# amp_ins.net
KiCad netlist of a schematic drawn in EAGLE
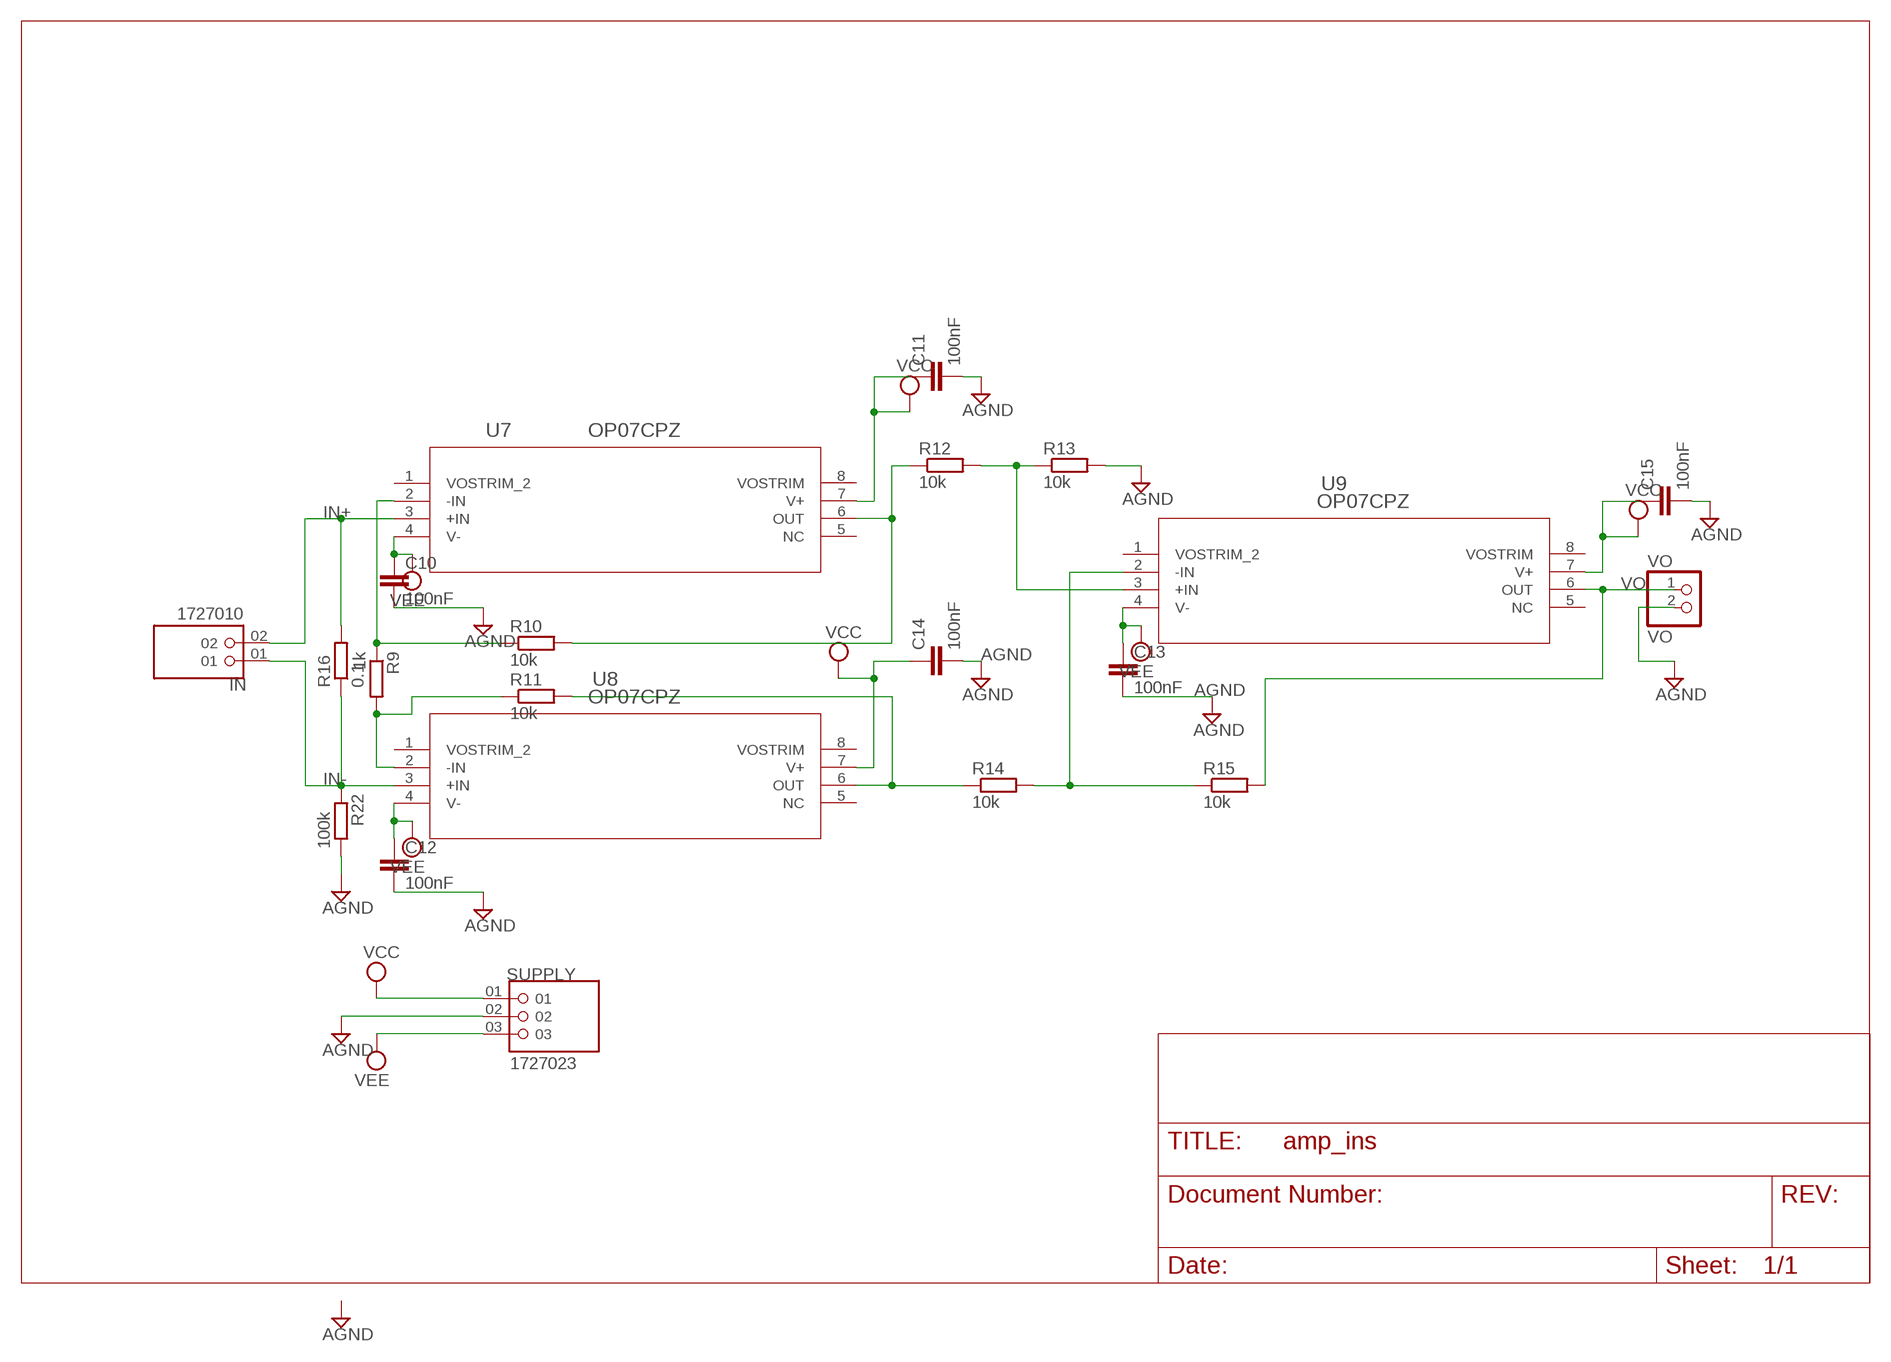
[diagram p0: schematic, sheet 1]

(export (version "E")
  (design (tool "Eeschema 10.0.6"))
  (components
    (comp (ref "C10")
      (value "100nF")
      (footprint "eagle-import:C075-042X103")
      (libsource (lib "eagle-import") (part "C-EU075-042X103"))
    )
    (comp (ref "C11")
      (value "100nF")
      (footprint "eagle-import:C075-042X103")
      (libsource (lib "eagle-import") (part "C-EU075-042X103"))
    )
    (comp (ref "C12")
      (value "100nF")
      (footprint "eagle-import:C075-042X103")
      (libsource (lib "eagle-import") (part "C-EU075-042X103"))
    )
    (comp (ref "C13")
      (value "100nF")
      (footprint "eagle-import:C075-042X103")
      (libsource (lib "eagle-import") (part "C-EU075-042X103"))
    )
    (comp (ref "C14")
      (value "100nF")
      (footprint "eagle-import:C075-042X103")
      (libsource (lib "eagle-import") (part "C-EU075-042X103"))
    )
    (comp (ref "C15")
      (value "100nF")
      (footprint "eagle-import:C075-042X103")
      (libsource (lib "eagle-import") (part "C-EU075-042X103"))
    )
    (comp (ref "IN")
      (value "1727010")
      (footprint "eagle-import:PHOENIX_1727010")
      (fields (field (name "MANUFACTURER") "Phoenix Contact"))
      (libsource (lib "eagle-import") (part "1727010"))
    )
    (comp (ref "R9")
      (value "1k")
      (footprint "eagle-import:0207_10")
      (libsource (lib "eagle-import") (part "R-EU_0207/10"))
    )
    (comp (ref "R10")
      (value "10k")
      (footprint "eagle-import:0207_10")
      (libsource (lib "eagle-import") (part "R-EU_0207/10"))
    )
    (comp (ref "R11")
      (value "10k")
      (footprint "eagle-import:0207_10")
      (libsource (lib "eagle-import") (part "R-EU_0207/10"))
    )
    (comp (ref "R12")
      (value "10k")
      (footprint "eagle-import:0207_10")
      (libsource (lib "eagle-import") (part "R-EU_0207/10"))
    )
    (comp (ref "R13")
      (value "10k")
      (footprint "eagle-import:0207_10")
      (libsource (lib "eagle-import") (part "R-EU_0207/10"))
    )
    (comp (ref "R14")
      (value "10k")
      (footprint "eagle-import:0207_10")
      (libsource (lib "eagle-import") (part "R-EU_0207/10"))
    )
    (comp (ref "R15")
      (value "10k")
      (footprint "eagle-import:0207_10")
      (libsource (lib "eagle-import") (part "R-EU_0207/10"))
    )
    (comp (ref "R16")
      (value "0.1")
      (footprint "eagle-import:0617_17")
      (libsource (lib "eagle-import") (part "R-EU_0617/17"))
    )
    (comp (ref "R22")
      (value "100k")
      (footprint "eagle-import:0207_10")
      (libsource (lib "eagle-import") (part "R-EU_0207/10"))
    )
    (comp (ref "SUPPLY")
      (value "1727023")
      (footprint "eagle-import:PHOENIX_1727023")
      (fields (field (name "MANUFACTURER") "Phoenix Contact"))
      (libsource (lib "eagle-import") (part "1727023"))
    )
    (comp (ref "U7")
      (value "OP07CPZ")
      (footprint "eagle-import:N_8_ADI")
      (fields (field (name "COPYRIGHT") "Copyright (C) 2024 Ultra Librarian. All rights reserved."))
      (libsource (lib "eagle-import") (part "OP07CPZ"))
    )
    (comp (ref "U8")
      (value "OP07CPZ")
      (footprint "eagle-import:N_8_ADI")
      (fields (field (name "COPYRIGHT") "Copyright (C) 2024 Ultra Librarian. All rights reserved."))
      (libsource (lib "eagle-import") (part "OP07CPZ"))
    )
    (comp (ref "U9")
      (value "OP07CPZ")
      (footprint "eagle-import:N_8_ADI")
      (fields (field (name "COPYRIGHT") "Copyright (C) 2024 Ultra Librarian. All rights reserved."))
      (libsource (lib "eagle-import") (part "OP07CPZ"))
    )
    (comp (ref "VO")
      (value "VO")
      (footprint "eagle-import:1X02")
      (libsource (lib "eagle-import") (part "PINHD-1X2"))
    )
  )
  (nets
    (net (code "1") (name "/IN+") (class "Default")
      (node (ref "IN") (pin "02") (pinfunction "02_02") (pintype "passive"))
      (node (ref "R16") (pin "2") (pinfunction "2_2") (pintype "passive"))
      (node (ref "U7") (pin "3") (pinfunction "+IN_3") (pintype "passive"))
    )
    (net (code "2") (name "/IN-") (class "Default")
      (node (ref "IN") (pin "01") (pinfunction "01_01") (pintype "passive"))
      (node (ref "R16") (pin "1") (pinfunction "1_1") (pintype "passive"))
      (node (ref "R22") (pin "1") (pinfunction "1_1") (pintype "passive"))
      (node (ref "U8") (pin "3") (pinfunction "+IN_3") (pintype "passive"))
    )
    (net (code "3") (name "/VO") (class "Default")
      (node (ref "R15") (pin "2") (pinfunction "2_2") (pintype "passive"))
      (node (ref "U9") (pin "6") (pinfunction "OUT_6") (pintype "passive"))
      (node (ref "VO") (pin "1") (pinfunction "1_1") (pintype "passive"))
    )
    (net (code "4") (name "AGND") (class "Default")
      (node (ref "C10") (pin "2") (pinfunction "2_2") (pintype "passive"))
      (node (ref "C11") (pin "2") (pinfunction "2_2") (pintype "passive"))
      (node (ref "C12") (pin "2") (pinfunction "2_2") (pintype "passive"))
      (node (ref "C13") (pin "2") (pinfunction "2_2") (pintype "passive"))
      (node (ref "C14") (pin "2") (pinfunction "2_2") (pintype "passive"))
      (node (ref "C15") (pin "2") (pinfunction "2_2") (pintype "passive"))
      (node (ref "R13") (pin "2") (pinfunction "2_2") (pintype "passive"))
      (node (ref "R22") (pin "2") (pinfunction "2_2") (pintype "passive"))
      (node (ref "SUPPLY") (pin "02") (pinfunction "02_02") (pintype "passive"))
      (node (ref "VO") (pin "2") (pinfunction "2_2") (pintype "passive"))
    )
    (net (code "5") (name "Net-(U7--IN)") (class "Default")
      (node (ref "R10") (pin "1") (pinfunction "1_1") (pintype "passive"))
      (node (ref "R9") (pin "1") (pinfunction "1_1") (pintype "passive"))
      (node (ref "U7") (pin "2") (pinfunction "-IN_2") (pintype "passive"))
    )
    (net (code "6") (name "Net-(U7-OUT)") (class "Default")
      (node (ref "R10") (pin "2") (pinfunction "2_2") (pintype "passive"))
      (node (ref "R12") (pin "1") (pinfunction "1_1") (pintype "passive"))
      (node (ref "U7") (pin "6") (pinfunction "OUT_6") (pintype "passive"))
    )
    (net (code "7") (name "Net-(U8--IN)") (class "Default")
      (node (ref "R11") (pin "1") (pinfunction "1_1") (pintype "passive"))
      (node (ref "R9") (pin "2") (pinfunction "2_2") (pintype "passive"))
      (node (ref "U8") (pin "2") (pinfunction "-IN_2") (pintype "passive"))
    )
    (net (code "8") (name "Net-(U8-OUT)") (class "Default")
      (node (ref "R11") (pin "2") (pinfunction "2_2") (pintype "passive"))
      (node (ref "R14") (pin "1") (pinfunction "1_1") (pintype "passive"))
      (node (ref "U8") (pin "6") (pinfunction "OUT_6") (pintype "passive"))
    )
    (net (code "9") (name "Net-(U9-+IN)") (class "Default")
      (node (ref "R12") (pin "2") (pinfunction "2_2") (pintype "passive"))
      (node (ref "R13") (pin "1") (pinfunction "1_1") (pintype "passive"))
      (node (ref "U9") (pin "3") (pinfunction "+IN_3") (pintype "passive"))
    )
    (net (code "10") (name "Net-(U9--IN)") (class "Default")
      (node (ref "R14") (pin "2") (pinfunction "2_2") (pintype "passive"))
      (node (ref "R15") (pin "1") (pinfunction "1_1") (pintype "passive"))
      (node (ref "U9") (pin "2") (pinfunction "-IN_2") (pintype "passive"))
    )
    (net (code "11") (name "VCC") (class "Default")
      (node (ref "C11") (pin "1") (pinfunction "1_1") (pintype "passive"))
      (node (ref "C14") (pin "1") (pinfunction "1_1") (pintype "passive"))
      (node (ref "C15") (pin "1") (pinfunction "1_1") (pintype "passive"))
      (node (ref "SUPPLY") (pin "01") (pinfunction "01_01") (pintype "passive"))
      (node (ref "U7") (pin "7") (pinfunction "V+_7") (pintype "power_in"))
      (node (ref "U8") (pin "7") (pinfunction "V+_7") (pintype "power_in"))
      (node (ref "U9") (pin "7") (pinfunction "V+_7") (pintype "power_in"))
    )
    (net (code "12") (name "VEE") (class "Default")
      (node (ref "C10") (pin "1") (pinfunction "1_1") (pintype "passive"))
      (node (ref "C12") (pin "1") (pinfunction "1_1") (pintype "passive"))
      (node (ref "C13") (pin "1") (pinfunction "1_1") (pintype "passive"))
      (node (ref "SUPPLY") (pin "03") (pinfunction "03_03") (pintype "passive"))
      (node (ref "U7") (pin "4") (pinfunction "V-_4") (pintype "power_in"))
      (node (ref "U8") (pin "4") (pinfunction "V-_4") (pintype "power_in"))
      (node (ref "U9") (pin "4") (pinfunction "V-_4") (pintype "power_in"))
    )
    (net (code "13") (name "unconnected-(U7-NC-Pad5)") (class "Default")
      (node (ref "U7") (pin "5") (pinfunction "NC_5") (pintype "passive"))
    )
    (net (code "14") (name "unconnected-(U7-VOSTRIM-Pad8)") (class "Default")
      (node (ref "U7") (pin "8") (pinfunction "VOSTRIM_8") (pintype "passive"))
    )
    (net (code "15") (name "unconnected-(U7-VOSTRIM_2-Pad1)") (class "Default")
      (node (ref "U7") (pin "1") (pinfunction "VOSTRIM_2_1") (pintype "passive"))
    )
    (net (code "16") (name "unconnected-(U8-NC-Pad5)") (class "Default")
      (node (ref "U8") (pin "5") (pinfunction "NC_5") (pintype "passive"))
    )
    (net (code "17") (name "unconnected-(U8-VOSTRIM-Pad8)") (class "Default")
      (node (ref "U8") (pin "8") (pinfunction "VOSTRIM_8") (pintype "passive"))
    )
    (net (code "18") (name "unconnected-(U8-VOSTRIM_2-Pad1)") (class "Default")
      (node (ref "U8") (pin "1") (pinfunction "VOSTRIM_2_1") (pintype "passive"))
    )
    (net (code "19") (name "unconnected-(U9-NC-Pad5)") (class "Default")
      (node (ref "U9") (pin "5") (pinfunction "NC_5") (pintype "passive"))
    )
    (net (code "20") (name "unconnected-(U9-VOSTRIM-Pad8)") (class "Default")
      (node (ref "U9") (pin "8") (pinfunction "VOSTRIM_8") (pintype "passive"))
    )
    (net (code "21") (name "unconnected-(U9-VOSTRIM_2-Pad1)") (class "Default")
      (node (ref "U9") (pin "1") (pinfunction "VOSTRIM_2_1") (pintype "passive"))
    )
  )
)
